# BATT_INPUT_TEST_BED_v3.net
KiCad netlist of a schematic drawn in EAGLE
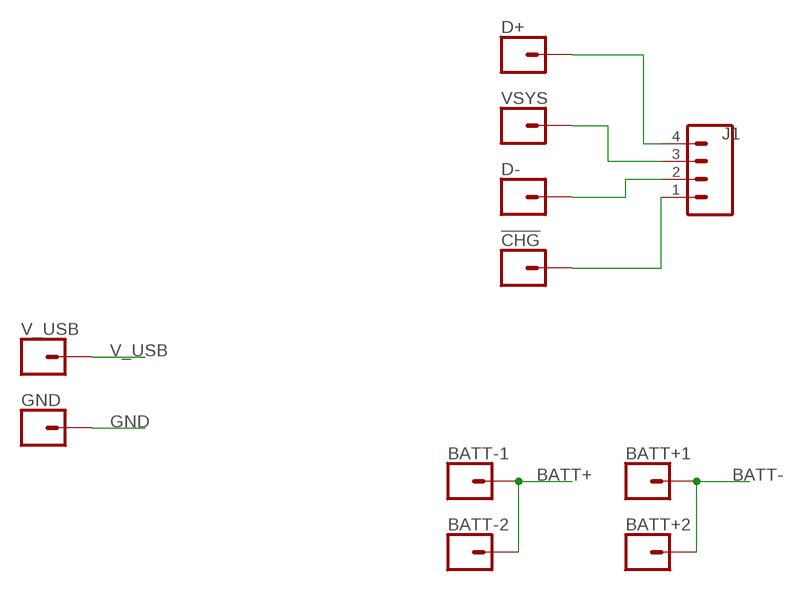
[diagram p0: schematic, sheet 1]

(export (version "E")
  (design (tool "Eeschema 10.0.6"))
  (components
    (comp (ref "!CHG!")
      (value "CONN_01POGOPIN_HOLE_LARGE")
      (footprint "eagle-import:1X01_POGOPIN_HOLE_0.061_DIA")
      (libsource (lib "eagle-import") (part "CONN_01POGOPIN_HOLE_LARGE"))
    )
    (comp (ref "BATT+1")
      (value "CONN_01POGOPIN_HOLE_LARGE")
      (footprint "eagle-import:1X01_POGOPIN_HOLE_0.061_DIA")
      (libsource (lib "eagle-import") (part "CONN_01POGOPIN_HOLE_LARGE"))
    )
    (comp (ref "BATT+2")
      (value "CONN_01POGOPIN_HOLE_LARGE")
      (footprint "eagle-import:1X01_POGOPIN_HOLE_0.061_DIA")
      (libsource (lib "eagle-import") (part "CONN_01POGOPIN_HOLE_LARGE"))
    )
    (comp (ref "BATT-1")
      (value "CONN_01POGOPIN_HOLE_LARGE")
      (footprint "eagle-import:1X01_POGOPIN_HOLE_0.061_DIA")
      (libsource (lib "eagle-import") (part "CONN_01POGOPIN_HOLE_LARGE"))
    )
    (comp (ref "BATT-2")
      (value "CONN_01POGOPIN_HOLE_LARGE")
      (footprint "eagle-import:1X01_POGOPIN_HOLE_0.061_DIA")
      (libsource (lib "eagle-import") (part "CONN_01POGOPIN_HOLE_LARGE"))
    )
    (comp (ref "D+")
      (value "CONN_01POGOPIN_HOLE_LARGE")
      (footprint "eagle-import:1X01_POGOPIN_HOLE_0.061_DIA")
      (libsource (lib "eagle-import") (part "CONN_01POGOPIN_HOLE_LARGE"))
    )
    (comp (ref "D-")
      (value "CONN_01POGOPIN_HOLE_LARGE")
      (footprint "eagle-import:1X01_POGOPIN_HOLE_0.061_DIA")
      (libsource (lib "eagle-import") (part "CONN_01POGOPIN_HOLE_LARGE"))
    )
    (comp (ref "GND")
      (value "CONN_01POGOPIN_HOLE_LARGE")
      (footprint "eagle-import:1X01_POGOPIN_HOLE_0.061_DIA")
      (libsource (lib "eagle-import") (part "CONN_01POGOPIN_HOLE_LARGE"))
    )
    (comp (ref "J1")
      (value "FEMALE 2x3")
      (footprint "eagle-import:1X04")
      (libsource (lib "eagle-import") (part "CONN_04"))
    )
    (comp (ref "VSYS")
      (value "CONN_01POGOPIN_HOLE_LARGE")
      (footprint "eagle-import:1X01_POGOPIN_HOLE_0.061_DIA")
      (libsource (lib "eagle-import") (part "CONN_01POGOPIN_HOLE_LARGE"))
    )
    (comp (ref "V_USB")
      (value "CONN_01POGOPIN_HOLE_LARGE")
      (footprint "eagle-import:1X01_POGOPIN_HOLE_0.061_DIA")
      (libsource (lib "eagle-import") (part "CONN_01POGOPIN_HOLE_LARGE"))
    )
  )
  (nets
    (net (code "1") (name "/BATT+") (class "Default")
      (node (ref "BATT-1") (pin "2") (pinfunction "1_2") (pintype "passive"))
      (node (ref "BATT-2") (pin "2") (pinfunction "1_2") (pintype "passive"))
    )
    (net (code "2") (name "/BATT-") (class "Default")
      (node (ref "BATT+1") (pin "2") (pinfunction "1_2") (pintype "passive"))
      (node (ref "BATT+2") (pin "2") (pinfunction "1_2") (pintype "passive"))
    )
    (net (code "3") (name "/GND") (class "Default")
      (node (ref "GND") (pin "2") (pinfunction "1_2") (pintype "passive"))
    )
    (net (code "4") (name "/V_USB") (class "Default")
      (node (ref "V_USB") (pin "2") (pinfunction "1_2") (pintype "passive"))
    )
    (net (code "5") (name "Net-(!CHG!-1)") (class "Default")
      (node (ref "!CHG!") (pin "2") (pinfunction "1_2") (pintype "passive"))
      (node (ref "J1") (pin "1") (pinfunction "1_1") (pintype "passive"))
    )
    (net (code "6") (name "Net-(D+-1)") (class "Default")
      (node (ref "D+") (pin "2") (pinfunction "1_2") (pintype "passive"))
      (node (ref "J1") (pin "4") (pinfunction "4_4") (pintype "passive"))
    )
    (net (code "7") (name "Net-(D--1)") (class "Default")
      (node (ref "D-") (pin "2") (pinfunction "1_2") (pintype "passive"))
      (node (ref "J1") (pin "2") (pinfunction "2_2") (pintype "passive"))
    )
    (net (code "8") (name "Net-(VSYS-1)") (class "Default")
      (node (ref "J1") (pin "3") (pinfunction "3_3") (pintype "passive"))
      (node (ref "VSYS") (pin "2") (pinfunction "1_2") (pintype "passive"))
    )
  )
)
